# FluoroDuino.net
KiCad netlist of a schematic drawn in EAGLE
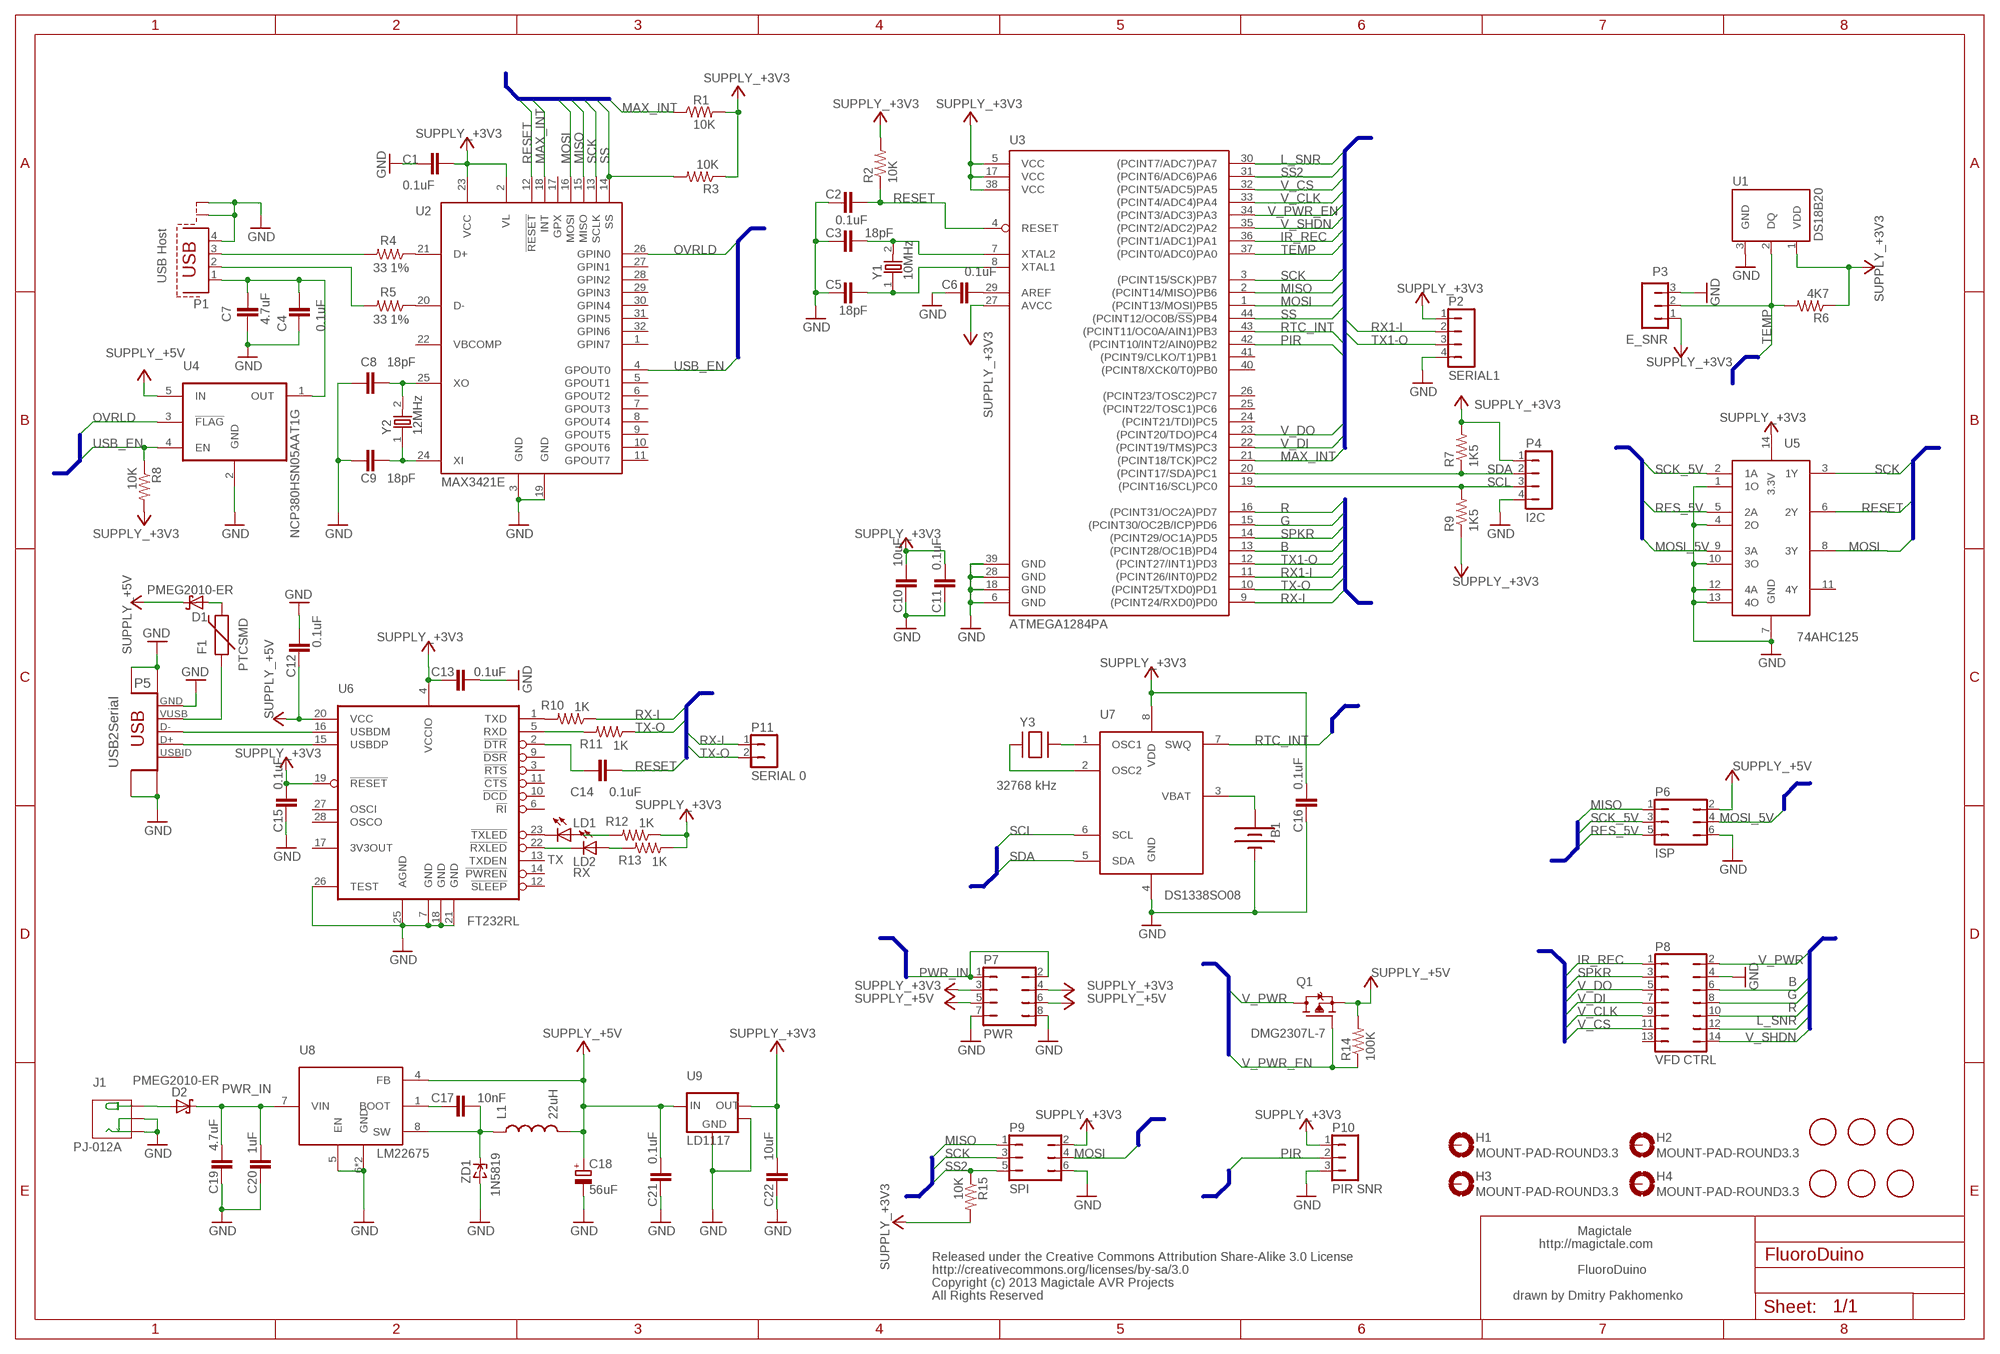
[diagram p0: schematic, sheet 1]

(export (version "E")
  (design (tool "Eeschema 10.0.6"))
  (components
    (comp (ref "B1")
      (value "BATTERY20PTH")
      (footprint "eagle-import:BATTCOM_20MM_PTH")
      (libsource (lib "eagle-import") (part "BATTERY20PTH"))
    )
    (comp (ref "C1")
      (value "0.1uF")
      (footprint "eagle-import:C1206")
      (libsource (lib "eagle-import") (part "CAPACITOR_NPOL-1206"))
    )
    (comp (ref "C2")
      (value "0.1uF")
      (footprint "eagle-import:C1206")
      (libsource (lib "eagle-import") (part "CAPACITOR_NPOL-1206"))
    )
    (comp (ref "C3")
      (value "18pF")
      (footprint "eagle-import:C1206")
      (libsource (lib "eagle-import") (part "CAPACITOR_NPOL-1206"))
    )
    (comp (ref "C4")
      (value "0.1uF")
      (footprint "eagle-import:C1206")
      (libsource (lib "eagle-import") (part "CAPACITOR_NPOL-1206"))
    )
    (comp (ref "C5")
      (value "18pF")
      (footprint "eagle-import:C1206")
      (libsource (lib "eagle-import") (part "CAPACITOR_NPOL-1206"))
    )
    (comp (ref "C6")
      (value "0.1uF")
      (footprint "eagle-import:C1206")
      (libsource (lib "eagle-import") (part "CAPACITOR_NPOL-1206"))
    )
    (comp (ref "C7")
      (value "4.7uF")
      (footprint "eagle-import:C1206")
      (libsource (lib "eagle-import") (part "CAPACITOR_NPOL-1206"))
    )
    (comp (ref "C8")
      (value "18pF")
      (footprint "eagle-import:C1206")
      (libsource (lib "eagle-import") (part "CAPACITOR_NPOL-1206"))
    )
    (comp (ref "C9")
      (value "18pF")
      (footprint "eagle-import:C1206")
      (libsource (lib "eagle-import") (part "CAPACITOR_NPOL-1206"))
    )
    (comp (ref "C10")
      (value "10uF")
      (footprint "eagle-import:C1206")
      (libsource (lib "eagle-import") (part "CAPACITOR_NPOL-1206"))
    )
    (comp (ref "C11")
      (value "0.1uF")
      (footprint "eagle-import:C1206")
      (libsource (lib "eagle-import") (part "CAPACITOR_NPOL-1206"))
    )
    (comp (ref "C12")
      (value "0.1uF")
      (footprint "eagle-import:C1206")
      (libsource (lib "eagle-import") (part "CAPACITOR_NPOL-1206"))
    )
    (comp (ref "C13")
      (value "0.1uF")
      (footprint "eagle-import:C1206")
      (libsource (lib "eagle-import") (part "CAPACITOR_NPOL-1206"))
    )
    (comp (ref "C14")
      (value "0.1uF")
      (footprint "eagle-import:C1206")
      (libsource (lib "eagle-import") (part "CAPACITOR_NPOL-1206"))
    )
    (comp (ref "C15")
      (value "0.1uF")
      (footprint "eagle-import:C1206")
      (libsource (lib "eagle-import") (part "CAPACITOR_NPOL-1206"))
    )
    (comp (ref "C16")
      (value "0.1uF")
      (footprint "eagle-import:C1206")
      (libsource (lib "eagle-import") (part "CAPACITOR_NPOL-1206"))
    )
    (comp (ref "C17")
      (value "10nF")
      (footprint "eagle-import:C1206")
      (libsource (lib "eagle-import") (part "CAPACITOR_NPOL-1206"))
    )
    (comp (ref "C18")
      (value "56uF")
      (footprint "eagle-import:PANASONIC_C")
      (libsource (lib "eagle-import") (part "CAPACITOR_POL"))
    )
    (comp (ref "C19")
      (value "4.7uF")
      (footprint "eagle-import:C1206")
      (libsource (lib "eagle-import") (part "CAPACITOR_NPOL-1206"))
    )
    (comp (ref "C20")
      (value "1uF")
      (footprint "eagle-import:C1206")
      (libsource (lib "eagle-import") (part "CAPACITOR_NPOL-1206"))
    )
    (comp (ref "C21")
      (value "0.1uF")
      (footprint "eagle-import:C1206")
      (libsource (lib "eagle-import") (part "CAPACITOR_NPOL-1206"))
    )
    (comp (ref "C22")
      (value "10uF")
      (footprint "eagle-import:C1206")
      (libsource (lib "eagle-import") (part "CAPACITOR_NPOL-1206"))
    )
    (comp (ref "D1")
      (value "PMEG2010-ER")
      (footprint "eagle-import:SOD123")
      (libsource (lib "eagle-import") (part "PMEG2010-ER"))
    )
    (comp (ref "D2")
      (value "PMEG2010-ER")
      (footprint "eagle-import:SOD123")
      (libsource (lib "eagle-import") (part "PMEG2010-ER"))
    )
    (comp (ref "F1")
      (value "PTCSMD")
      (footprint "eagle-import:PTC-1206")
      (libsource (lib "eagle-import") (part "PTCSMD"))
    )
    (comp (ref "FIDUTIAL1")
      (value "FIDUCIAL")
      (footprint "eagle-import:FIDUCIAL_1MM")
      (libsource (lib "eagle-import") (part "FIDUCIAL"))
    )
    (comp (ref "FIDUTIAL2")
      (value "FIDUCIAL")
      (footprint "eagle-import:FIDUCIAL_1MM")
      (libsource (lib "eagle-import") (part "FIDUCIAL"))
    )
    (comp (ref "FIDUTIAL3")
      (value "FIDUCIAL")
      (footprint "eagle-import:FIDUCIAL_1MM")
      (libsource (lib "eagle-import") (part "FIDUCIAL"))
    )
    (comp (ref "FIDUTIAL4")
      (value "FIDUCIAL")
      (footprint "eagle-import:FIDUCIAL_1MM")
      (libsource (lib "eagle-import") (part "FIDUCIAL"))
    )
    (comp (ref "FIDUTIAL5")
      (value "FIDUCIAL")
      (footprint "eagle-import:FIDUCIAL_1MM")
      (libsource (lib "eagle-import") (part "FIDUCIAL"))
    )
    (comp (ref "FIDUTIAL6")
      (value "FIDUCIAL")
      (footprint "eagle-import:FIDUCIAL_1MM")
      (libsource (lib "eagle-import") (part "FIDUCIAL"))
    )
    (comp (ref "H1")
      (value "MOUNT-PAD-ROUND3.3")
      (footprint "eagle-import:3,3-PAD")
      (libsource (lib "eagle-import") (part "MOUNT-PAD-ROUND3.3"))
    )
    (comp (ref "H2")
      (value "MOUNT-PAD-ROUND3.3")
      (footprint "eagle-import:3,3-PAD")
      (libsource (lib "eagle-import") (part "MOUNT-PAD-ROUND3.3"))
    )
    (comp (ref "H3")
      (value "MOUNT-PAD-ROUND3.3")
      (footprint "eagle-import:3,3-PAD")
      (libsource (lib "eagle-import") (part "MOUNT-PAD-ROUND3.3"))
    )
    (comp (ref "H4")
      (value "MOUNT-PAD-ROUND3.3")
      (footprint "eagle-import:3,3-PAD")
      (libsource (lib "eagle-import") (part "MOUNT-PAD-ROUND3.3"))
    )
    (comp (ref "J1")
      (value "PJ-012A")
      (footprint "eagle-import:PJ-012A")
      (libsource (lib "eagle-import") (part "PJ-012A"))
    )
    (comp (ref "L1")
      (value "22uH")
      (footprint "eagle-import:VLC6045")
      (libsource (lib "eagle-import") (part "INDUCTOR"))
    )
    (comp (ref "LD1")
      (value "TX")
      (footprint "eagle-import:CHIPLED_1206")
      (libsource (lib "eagle-import") (part "LEDCHIPLED_1206"))
    )
    (comp (ref "LD2")
      (value "RX")
      (footprint "eagle-import:CHIPLED_1206")
      (libsource (lib "eagle-import") (part "LEDCHIPLED_1206"))
    )
    (comp (ref "P1")
      (value "USB Host")
      (footprint "eagle-import:USB-A-VER")
      (libsource (lib "eagle-import") (part "USB-AVERT"))
    )
    (comp (ref "P2")
      (value "SERIAL1")
      (footprint "eagle-import:CONN_HEADER_1X04")
      (libsource (lib "eagle-import") (part "CONN_HEADER_1X04STRAIGHT"))
    )
    (comp (ref "P3")
      (value "E_SNR")
      (footprint "eagle-import:CONN_HEADER_1X03")
      (fields (field (name "F_PIN") "1") (field (name "L_PIN") "3"))
      (libsource (lib "eagle-import") (part "CONN_HEADER_1X03STRAIGHT"))
    )
    (comp (ref "P4")
      (value "I2C")
      (footprint "eagle-import:CONN_HEADER_1X04")
      (fields (field (name "F_PIN") "1") (field (name "L_PIN") "4"))
      (libsource (lib "eagle-import") (part "CONN_HEADER_1X04STRAIGHT"))
    )
    (comp (ref "P5")
      (value "USB2Serial")
      (footprint "eagle-import:CONN_USB_MINI_RA")
      (fields (field (name "DIGIKEY") "732-2735-ND"))
      (libsource (lib "eagle-import") (part "CON-USB-F-MINI-B-RA"))
    )
    (comp (ref "P6")
      (value "ISP")
      (footprint "eagle-import:CONN_HEADER_2X03")
      (fields (field (name "F_PIN") "1") (field (name "L_PIN") "5"))
      (libsource (lib "eagle-import") (part "CONN_HEADER_2X03"))
    )
    (comp (ref "P7")
      (value "PWR")
      (footprint "eagle-import:CONN_HEADER_2X04")
      (fields (field (name "F_PIN") "1") (field (name "L_PIN") "7"))
      (libsource (lib "eagle-import") (part "CONN_HEADER_2X04"))
    )
    (comp (ref "P8")
      (value "VFD CTRL")
      (footprint "eagle-import:CONN_HEADER_2X07_F_MIRR")
      (libsource (lib "eagle-import") (part "CONN_HEADER_2X07F_MIRR"))
    )
    (comp (ref "P9")
      (value "SPI")
      (footprint "eagle-import:CONN_HEADER_2X03")
      (fields (field (name "F_PIN") "1") (field (name "L_PIN") "5"))
      (libsource (lib "eagle-import") (part "CONN_HEADER_2X03"))
    )
    (comp (ref "P10")
      (value "PIR SNR")
      (footprint "eagle-import:CONN_HEADER_1X03")
      (fields (field (name "F_PIN") "1") (field (name "L_PIN") "3"))
      (libsource (lib "eagle-import") (part "CONN_HEADER_1X03STRAIGHT"))
    )
    (comp (ref "P11")
      (value "SERIAL 0")
      (footprint "eagle-import:CONN_HEADER_1X02")
      (libsource (lib "eagle-import") (part "CONN_HEADER_1X02"))
    )
    (comp (ref "Q1")
      (value "DMG2307L-7")
      (footprint "eagle-import:SOT-23")
      (libsource (lib "eagle-import") (part "TRANSISTOR_FET_TSM2301CX"))
    )
    (comp (ref "R1")
      (value "10K")
      (footprint "eagle-import:R1206")
      (libsource (lib "eagle-import") (part "RESISTOR-1206"))
    )
    (comp (ref "R2")
      (value "10K")
      (footprint "eagle-import:R1206")
      (libsource (lib "eagle-import") (part "RESISTOR-1206"))
    )
    (comp (ref "R3")
      (value "10K")
      (footprint "eagle-import:R1206")
      (libsource (lib "eagle-import") (part "RESISTOR-1206"))
    )
    (comp (ref "R4")
      (value "33 1%")
      (footprint "eagle-import:R1206")
      (libsource (lib "eagle-import") (part "RESISTOR-1206"))
    )
    (comp (ref "R5")
      (value "33 1%")
      (footprint "eagle-import:R1206")
      (libsource (lib "eagle-import") (part "RESISTOR-1206"))
    )
    (comp (ref "R6")
      (value "4K7")
      (footprint "eagle-import:R1206")
      (libsource (lib "eagle-import") (part "RESISTOR-1206"))
    )
    (comp (ref "R7")
      (value "1K5")
      (footprint "eagle-import:R1206")
      (libsource (lib "eagle-import") (part "RESISTOR-1206"))
    )
    (comp (ref "R8")
      (value "10K")
      (footprint "eagle-import:R1206")
      (libsource (lib "eagle-import") (part "RESISTOR-1206"))
    )
    (comp (ref "R9")
      (value "1K5")
      (footprint "eagle-import:R1206")
      (libsource (lib "eagle-import") (part "RESISTOR-1206"))
    )
    (comp (ref "R10")
      (value "1K")
      (footprint "eagle-import:R1206")
      (libsource (lib "eagle-import") (part "RESISTOR-1206"))
    )
    (comp (ref "R11")
      (value "1K")
      (footprint "eagle-import:R1206")
      (libsource (lib "eagle-import") (part "RESISTOR-1206"))
    )
    (comp (ref "R12")
      (value "1K")
      (footprint "eagle-import:R1206")
      (libsource (lib "eagle-import") (part "RESISTOR-1206"))
    )
    (comp (ref "R13")
      (value "1K")
      (footprint "eagle-import:R1206")
      (libsource (lib "eagle-import") (part "RESISTOR-1206"))
    )
    (comp (ref "R14")
      (value "100K")
      (footprint "eagle-import:R1206")
      (libsource (lib "eagle-import") (part "RESISTOR-1206"))
    )
    (comp (ref "R15")
      (value "10K")
      (footprint "eagle-import:R1206")
      (libsource (lib "eagle-import") (part "RESISTOR-1206"))
    )
    (comp (ref "U$")
      (value "MT_LOGOCOMPACT")
      (footprint "eagle-import:MT_LOGO_COMPACT")
      (libsource (lib "eagle-import") (part "MT_LOGOCOMPACT"))
    )
    (comp (ref "U1")
      (value "DS18B20")
      (footprint "eagle-import:TO-92-AMMO")
      (libsource (lib "eagle-import") (part "DS18B20"))
    )
    (comp (ref "U2")
      (value "MAX3421E")
      (footprint "eagle-import:TQFP32-08")
      (libsource (lib "eagle-import") (part "MAXIM_MAX3421E"))
    )
    (comp (ref "U3")
      (value "ATMEGA1284PA")
      (footprint "eagle-import:TQFP44")
      (fields (field (name "MPN") "ATMEGA1284P-10AU"))
      (libsource (lib "eagle-import") (part "ATMEGA1284PA"))
    )
    (comp (ref "U4")
      (value "NCP380HSN05AAT1G")
      (footprint "eagle-import:SOT23-5")
      (libsource (lib "eagle-import") (part "POWERSW_FIX-SOT5-1"))
    )
    (comp (ref "U5")
      (value "74AHC125")
      (footprint "eagle-import:SO014")
      (libsource (lib "eagle-import") (part "CH_LOGIC_74125_33V-SO"))
    )
    (comp (ref "U6")
      (value "FT232RL")
      (footprint "eagle-import:SSOP-28")
      (libsource (lib "eagle-import") (part "IC_FT232RL"))
    )
    (comp (ref "U7")
      (value "DS1338SO08")
      (footprint "eagle-import:SO08")
      (libsource (lib "eagle-import") (part "ICS_DS1338SO08"))
    )
    (comp (ref "U8")
      (value "LM22675")
      (footprint "eagle-import:SO08_POWER_PAD")
      (libsource (lib "eagle-import") (part "ICS_LM22675"))
    )
    (comp (ref "U9")
      (value "LD1117")
      (footprint "eagle-import:SOT223")
      (libsource (lib "eagle-import") (part "V_REG_LD1117SOT223"))
    )
    (comp (ref "Y1")
      (value "10MHz")
      (footprint "eagle-import:XTAL_4X6")
      (libsource (lib "eagle-import") (part "OSC-XTAL-12M"))
    )
    (comp (ref "Y2")
      (value "12MHz")
      (footprint "eagle-import:XTAL_4X6")
      (libsource (lib "eagle-import") (part "OSC-XTAL-12M"))
    )
    (comp (ref "Y3")
      (value "32768 kHz")
      (footprint "eagle-import:XTAL3215")
      (libsource (lib "eagle-import") (part "XTAL-3.2X1.5"))
    )
    (comp (ref "ZD1")
      (value "1N5819")
      (footprint "eagle-import:SOD123")
      (libsource (lib "eagle-import") (part "ZENERSOD-123"))
    )
  )
  (nets
    (net (code "1") (name "/B") (class "Default")
      (node (ref "P8") (pin "6") (pinfunction "6_6") (pintype "passive"))
      (node (ref "U3") (pin "13") (pinfunction "(PCINT28/OC1B)PD4_13") (pintype "bidirectional"))
    )
    (net (code "2") (name "/G") (class "Default")
      (node (ref "P8") (pin "8") (pinfunction "8_8") (pintype "passive"))
      (node (ref "U3") (pin "15") (pinfunction "(PCINT30/OC2B/ICP)PD6_15") (pintype "bidirectional"))
    )
    (net (code "3") (name "/IR_REC") (class "Default")
      (node (ref "P8") (pin "1") (pinfunction "1_1") (pintype "passive"))
      (node (ref "U3") (pin "36") (pinfunction "(PCINT1/ADC1)PA1_36") (pintype "bidirectional"))
    )
    (net (code "4") (name "/L_SNR") (class "Default")
      (node (ref "P8") (pin "12") (pinfunction "12_12") (pintype "passive"))
      (node (ref "U3") (pin "30") (pinfunction "(PCINT7/ADC7)PA7_30") (pintype "bidirectional"))
    )
    (net (code "5") (name "/MAX_INT") (class "Default")
      (node (ref "R1") (pin "1") (pinfunction "1_1") (pintype "passive"))
      (node (ref "U2") (pin "18") (pinfunction "INT_18") (pintype "output"))
      (node (ref "U3") (pin "21") (pinfunction "(PCINT18/TCK)PC2_21") (pintype "output"))
    )
    (net (code "6") (name "/MISO") (class "Default")
      (node (ref "P6") (pin "1") (pinfunction "1_1") (pintype "passive"))
      (node (ref "P9") (pin "1") (pinfunction "1_1") (pintype "passive"))
      (node (ref "U2") (pin "15") (pinfunction "MISO_15") (pintype "output"))
      (node (ref "U3") (pin "2") (pinfunction "(PCINT14/MISO)PB6_2") (pintype "bidirectional"))
    )
    (net (code "7") (name "/MOSI") (class "Default")
      (node (ref "P9") (pin "4") (pinfunction "4_4") (pintype "passive"))
      (node (ref "U2") (pin "16") (pinfunction "MOSI_16") (pintype "input"))
      (node (ref "U3") (pin "1") (pinfunction "(PCINT13/MOSI)PB5_1") (pintype "bidirectional"))
      (node (ref "U5") (pin "8") (pinfunction "3Y_8") (pintype "output"))
    )
    (net (code "8") (name "/MOSI_5V") (class "Default")
      (node (ref "P6") (pin "4") (pinfunction "4_4") (pintype "passive"))
      (node (ref "U5") (pin "9") (pinfunction "3A_9") (pintype "input"))
    )
    (net (code "9") (name "/OVRLD") (class "Default")
      (node (ref "U2") (pin "26") (pinfunction "GPIN0_26") (pintype "input"))
      (node (ref "U4") (pin "3") (pinfunction "~{FLAG}_3") (pintype "bidirectional"))
    )
    (net (code "10") (name "/PIR") (class "Default")
      (node (ref "P10") (pin "2") (pinfunction "2_2") (pintype "passive"))
      (node (ref "U3") (pin "42") (pinfunction "(PCINT10/INT2/AIN0)PB2_42") (pintype "bidirectional"))
    )
    (net (code "11") (name "/PWR_IN") (class "Default")
      (node (ref "C19") (pin "2") (pinfunction "2_2") (pintype "passive"))
      (node (ref "C20") (pin "2") (pinfunction "2_2") (pintype "passive"))
      (node (ref "D2") (pin "C") (pinfunction "C_C") (pintype "passive"))
      (node (ref "P7") (pin "1") (pinfunction "1_1") (pintype "passive"))
      (node (ref "P7") (pin "2") (pinfunction "2_2") (pintype "passive"))
      (node (ref "U8") (pin "7") (pinfunction "VIN_7") (pintype "power_in"))
    )
    (net (code "12") (name "/R") (class "Default")
      (node (ref "P8") (pin "10") (pinfunction "10_10") (pintype "passive"))
      (node (ref "U3") (pin "16") (pinfunction "(PCINT31/OC2A)PD7_16") (pintype "bidirectional"))
    )
    (net (code "13") (name "/RESET") (class "Default")
      (node (ref "C14") (pin "1") (pinfunction "1_1") (pintype "passive"))
      (node (ref "C2") (pin "2") (pinfunction "2_2") (pintype "passive"))
      (node (ref "R2") (pin "1") (pinfunction "1_1") (pintype "passive"))
      (node (ref "U2") (pin "12") (pinfunction "~{RESET}_12") (pintype "input"))
      (node (ref "U3") (pin "4") (pinfunction "RESET_4") (pintype "input"))
      (node (ref "U5") (pin "6") (pinfunction "2Y_6") (pintype "output"))
    )
    (net (code "14") (name "/RES_5V") (class "Default")
      (node (ref "P6") (pin "5") (pinfunction "5_5") (pintype "passive"))
      (node (ref "U5") (pin "5") (pinfunction "2A_5") (pintype "input"))
    )
    (net (code "15") (name "/RTC_INT") (class "Default")
      (node (ref "U3") (pin "43") (pinfunction "(PCINT11/OC0A/AIN1)PB3_43") (pintype "bidirectional"))
      (node (ref "U7") (pin "7") (pinfunction "SWQ_7") (pintype "bidirectional"))
    )
    (net (code "16") (name "/RX-I") (class "Default")
      (node (ref "P11") (pin "1") (pinfunction "1_1") (pintype "passive"))
      (node (ref "R10") (pin "1") (pinfunction "1_1") (pintype "passive"))
      (node (ref "U3") (pin "9") (pinfunction "(PCINT24/RXD0)PD0_9") (pintype "bidirectional"))
    )
    (net (code "17") (name "/RX1-I") (class "Default")
      (node (ref "P2") (pin "2") (pinfunction "2_2") (pintype "passive"))
      (node (ref "U3") (pin "11") (pinfunction "(PCINT26/INT0)PD2_11") (pintype "bidirectional"))
    )
    (net (code "18") (name "/SCK") (class "Default")
      (node (ref "P9") (pin "3") (pinfunction "3_3") (pintype "passive"))
      (node (ref "U2") (pin "13") (pinfunction "SCLK_13") (pintype "input"))
      (node (ref "U3") (pin "3") (pinfunction "(PCINT15/SCK)PB7_3") (pintype "bidirectional"))
      (node (ref "U5") (pin "3") (pinfunction "1Y_3") (pintype "output"))
    )
    (net (code "19") (name "/SCK_5V") (class "Default")
      (node (ref "P6") (pin "3") (pinfunction "3_3") (pintype "passive"))
      (node (ref "U5") (pin "2") (pinfunction "1A_2") (pintype "input"))
    )
    (net (code "20") (name "/SCL") (class "Default")
      (node (ref "P4") (pin "3") (pinfunction "3_3") (pintype "passive"))
      (node (ref "R9") (pin "2") (pinfunction "2_2") (pintype "passive"))
      (node (ref "U3") (pin "19") (pinfunction "(PCINT16/SCL)PC0_19") (pintype "output"))
      (node (ref "U7") (pin "6") (pinfunction "SCL_6") (pintype "bidirectional"))
    )
    (net (code "21") (name "/SDA") (class "Default")
      (node (ref "P4") (pin "2") (pinfunction "2_2") (pintype "passive"))
      (node (ref "R7") (pin "1") (pinfunction "1_1") (pintype "passive"))
      (node (ref "U3") (pin "20") (pinfunction "(PCINT17/SDA)PC1_20") (pintype "output"))
      (node (ref "U7") (pin "5") (pinfunction "SDA_5") (pintype "bidirectional"))
    )
    (net (code "22") (name "/SPKR") (class "Default")
      (node (ref "P8") (pin "3") (pinfunction "3_3") (pintype "passive"))
      (node (ref "U3") (pin "14") (pinfunction "(PCINT29/OC1A)PD5_14") (pintype "bidirectional"))
    )
    (net (code "23") (name "/SS") (class "Default")
      (node (ref "R3") (pin "2") (pinfunction "2_2") (pintype "passive"))
      (node (ref "U2") (pin "14") (pinfunction "SS_14") (pintype "input"))
      (node (ref "U3") (pin "44") (pinfunction "(PCINT12/OC0B/~{SS})PB4_44") (pintype "bidirectional"))
    )
    (net (code "24") (name "/SS2") (class "Default")
      (node (ref "P9") (pin "5") (pinfunction "5_5") (pintype "passive"))
      (node (ref "R15") (pin "1") (pinfunction "1_1") (pintype "passive"))
      (node (ref "U3") (pin "31") (pinfunction "(PCINT6/ADC6)PA6_31") (pintype "bidirectional"))
    )
    (net (code "25") (name "/TEMP") (class "Default")
      (node (ref "P3") (pin "2") (pinfunction "2_2") (pintype "passive"))
      (node (ref "R6") (pin "2") (pinfunction "2_2") (pintype "passive"))
      (node (ref "U1") (pin "2") (pinfunction "DQ_2") (pintype "bidirectional"))
      (node (ref "U3") (pin "37") (pinfunction "(PCINT0/ADC0)PA0_37") (pintype "bidirectional"))
    )
    (net (code "26") (name "/TX-O") (class "Default")
      (node (ref "P11") (pin "2") (pinfunction "2_2") (pintype "passive"))
      (node (ref "R11") (pin "1") (pinfunction "1_1") (pintype "passive"))
      (node (ref "U3") (pin "10") (pinfunction "(PCINT25/TXD0)PD1_10") (pintype "bidirectional"))
    )
    (net (code "27") (name "/TX1-O") (class "Default")
      (node (ref "P2") (pin "3") (pinfunction "3_3") (pintype "passive"))
      (node (ref "U3") (pin "12") (pinfunction "(PCINT27/INT1)PD3_12") (pintype "bidirectional"))
    )
    (net (code "28") (name "/USB_EN") (class "Default")
      (node (ref "R8") (pin "1") (pinfunction "1_1") (pintype "passive"))
      (node (ref "U2") (pin "4") (pinfunction "GPOUT0_4") (pintype "output"))
      (node (ref "U4") (pin "4") (pinfunction "EN_4") (pintype "bidirectional"))
    )
    (net (code "29") (name "/V_CLK") (class "Default")
      (node (ref "P8") (pin "9") (pinfunction "9_9") (pintype "passive"))
      (node (ref "U3") (pin "33") (pinfunction "(PCINT4/ADC4)PA4_33") (pintype "bidirectional"))
    )
    (net (code "30") (name "/V_CS") (class "Default")
      (node (ref "P8") (pin "11") (pinfunction "11_11") (pintype "passive"))
      (node (ref "U3") (pin "32") (pinfunction "(PCINT5/ADC5)PA5_32") (pintype "bidirectional"))
    )
    (net (code "31") (name "/V_DI") (class "Default")
      (node (ref "P8") (pin "7") (pinfunction "7_7") (pintype "passive"))
      (node (ref "U3") (pin "22") (pinfunction "(PCINT19/TMS)PC3_22") (pintype "output"))
    )
    (net (code "32") (name "/V_DO") (class "Default")
      (node (ref "P8") (pin "5") (pinfunction "5_5") (pintype "passive"))
      (node (ref "U3") (pin "23") (pinfunction "(PCINT20/TDO)PC4_23") (pintype "output"))
    )
    (net (code "33") (name "/V_PWR") (class "Default")
      (node (ref "P8") (pin "2") (pinfunction "2_2") (pintype "passive"))
      (node (ref "Q1") (pin "3") (pinfunction "D_3") (pintype "passive"))
    )
    (net (code "34") (name "/V_PWR_EN") (class "Default")
      (node (ref "Q1") (pin "1") (pinfunction "G_1") (pintype "passive"))
      (node (ref "R14") (pin "1") (pinfunction "1_1") (pintype "passive"))
      (node (ref "U3") (pin "34") (pinfunction "(PCINT3/ADC3)PA3_34") (pintype "bidirectional"))
    )
    (net (code "35") (name "/V_SHDN") (class "Default")
      (node (ref "P8") (pin "14") (pinfunction "14_14") (pintype "passive"))
      (node (ref "U3") (pin "35") (pinfunction "(PCINT2/ADC2)PA2_35") (pintype "bidirectional"))
    )
    (net (code "36") (name "GND") (class "Default")
      (node (ref "B1") (pin "2") (pinfunction "-_2") (pintype "power_in"))
      (node (ref "C1") (pin "2") (pinfunction "2_2") (pintype "passive"))
      (node (ref "C10") (pin "1") (pinfunction "1_1") (pintype "passive"))
      (node (ref "C11") (pin "1") (pinfunction "1_1") (pintype "passive"))
      (node (ref "C12") (pin "2") (pinfunction "2_2") (pintype "passive"))
      (node (ref "C13") (pin "2") (pinfunction "2_2") (pintype "passive"))
      (node (ref "C15") (pin "1") (pinfunction "1_1") (pintype "passive"))
      (node (ref "C16") (pin "1") (pinfunction "1_1") (pintype "passive"))
      (node (ref "C18") (pin "-") (pinfunction "-_-") (pintype "passive"))
      (node (ref "C19") (pin "1") (pinfunction "1_1") (pintype "passive"))
      (node (ref "C2") (pin "1") (pinfunction "1_1") (pintype "passive"))
      (node (ref "C20") (pin "1") (pinfunction "1_1") (pintype "passive"))
      (node (ref "C21") (pin "1") (pinfunction "1_1") (pintype "passive"))
      (node (ref "C22") (pin "1") (pinfunction "1_1") (pintype "passive"))
      (node (ref "C3") (pin "1") (pinfunction "1_1") (pintype "passive"))
      (node (ref "C4") (pin "2") (pinfunction "2_2") (pintype "passive"))
      (node (ref "C5") (pin "1") (pinfunction "1_1") (pintype "passive"))
      (node (ref "C6") (pin "1") (pinfunction "1_1") (pintype "passive"))
      (node (ref "C7") (pin "1") (pinfunction "1_1") (pintype "passive"))
      (node (ref "C8") (pin "1") (pinfunction "1_1") (pintype "passive"))
      (node (ref "C9") (pin "1") (pinfunction "1_1") (pintype "passive"))
      (node (ref "J1") (pin "2") (pinfunction "2_2") (pintype "bidirectional"))
      (node (ref "J1") (pin "3") (pinfunction "3_3") (pintype "bidirectional"))
      (node (ref "P1") (pin "4") (pinfunction "4_4") (pintype "passive"))
      (node (ref "P1") (pin "S1") (pinfunction "S1_S1") (pintype "passive"))
      (node (ref "P1") (pin "S2") (pinfunction "S2_S2") (pintype "passive"))
      (node (ref "P10") (pin "3") (pinfunction "3_3") (pintype "passive"))
      (node (ref "P2") (pin "4") (pinfunction "4_4") (pintype "passive"))
      (node (ref "P3") (pin "3") (pinfunction "3_3") (pintype "passive"))
      (node (ref "P4") (pin "4") (pinfunction "4_4") (pintype "passive"))
      (node (ref "P5") (pin "5") (pinfunction "GND_5") (pintype "bidirectional"))
      (node (ref "P5") (pin "S1") (pinfunction "BODY_S1") (pintype "tri_state"))
      (node (ref "P5") (pin "S2") (pinfunction "BODY_S2") (pintype "tri_state"))
      (node (ref "P5") (pin "S3") (pinfunction "BODY_S3") (pintype "tri_state"))
      (node (ref "P5") (pin "S4") (pinfunction "BODY_S4") (pintype "tri_state"))
      (node (ref "P6") (pin "6") (pinfunction "6_6") (pintype "passive"))
      (node (ref "P7") (pin "7") (pinfunction "7_7") (pintype "passive"))
      (node (ref "P7") (pin "8") (pinfunction "8_8") (pintype "passive"))
      (node (ref "P8") (pin "4") (pinfunction "4_4") (pintype "passive"))
      (node (ref "P9") (pin "6") (pinfunction "6_6") (pintype "passive"))
      (node (ref "U1") (pin "3") (pinfunction "GND_3") (pintype "power_in"))
      (node (ref "U2") (pin "19") (pinfunction "GND_19") (pintype "power_in"))
      (node (ref "U2") (pin "3") (pinfunction "GND_3") (pintype "power_in"))
      (node (ref "U3") (pin "18") (pinfunction "GND_18") (pintype "power_in"))
      (node (ref "U3") (pin "28") (pinfunction "GND_28") (pintype "power_in"))
      (node (ref "U3") (pin "39") (pinfunction "GND_39") (pintype "power_in"))
      (node (ref "U3") (pin "6") (pinfunction "GND_6") (pintype "power_in"))
      (node (ref "U4") (pin "2") (pinfunction "GND_2") (pintype "bidirectional"))
      (node (ref "U5") (pin "1") (pinfunction "1O_1") (pintype "input"))
      (node (ref "U5") (pin "10") (pinfunction "3O_10") (pintype "input"))
      (node (ref "U5") (pin "12") (pinfunction "4A_12") (pintype "input"))
      (node (ref "U5") (pin "13") (pinfunction "4O_13") (pintype "input"))
      (node (ref "U5") (pin "4") (pinfunction "2O_4") (pintype "input"))
      (node (ref "U5") (pin "7") (pinfunction "GND_7") (pintype "passive"))
      (node (ref "U6") (pin "18") (pinfunction "GND_18") (pintype "bidirectional"))
      (node (ref "U6") (pin "21") (pinfunction "GND_21") (pintype "bidirectional"))
      (node (ref "U6") (pin "25") (pinfunction "AGND_25") (pintype "bidirectional"))
      (node (ref "U6") (pin "26") (pinfunction "TEST_26") (pintype "bidirectional"))
      (node (ref "U6") (pin "7") (pinfunction "GND_7") (pintype "bidirectional"))
      (node (ref "U7") (pin "4") (pinfunction "GND_4") (pintype "bidirectional"))
      (node (ref "U8") (pin "5") (pinfunction "EN_5") (pintype "bidirectional"))
      (node (ref "U8") (pin "6") (pinfunction "GND_6") (pintype "power_in"))
      (node (ref "U8") (pin "BODY@1") (pinfunction "GND_BODY@1") (pintype "power_in"))
      (node (ref "U9") (pin "1") (pinfunction "GND_1") (pintype "input"))
      (node (ref "U9") (pin "4") (pinfunction "OUT_4") (pintype "output"))
      (node (ref "ZD1") (pin "A") (pinfunction "A_A") (pintype "passive"))
    )
    (net (code "37") (name "Net-(B1-+)") (class "Default")
      (node (ref "B1") (pin "1") (pinfunction "+_1") (pintype "power_in"))
      (node (ref "U7") (pin "3") (pinfunction "VBAT_3") (pintype "bidirectional"))
    )
    (net (code "38") (name "Net-(D1-PadA)") (class "Default")
      (node (ref "D1") (pin "A") (pinfunction "A_A") (pintype "passive"))
      (node (ref "F1") (pin "2") (pinfunction "2_2") (pintype "bidirectional"))
    )
    (net (code "39") (name "Net-(D2-PadA)") (class "Default")
      (node (ref "D2") (pin "A") (pinfunction "A_A") (pintype "passive"))
      (node (ref "J1") (pin "1") (pinfunction "1_1") (pintype "bidirectional"))
    )
    (net (code "40") (name "Net-(LD1-PadA)") (class "Default")
      (node (ref "LD1") (pin "A") (pinfunction "A_A") (pintype "passive"))
      (node (ref "R12") (pin "2") (pinfunction "2_2") (pintype "passive"))
    )
    (net (code "41") (name "Net-(LD2-PadA)") (class "Default")
      (node (ref "LD2") (pin "A") (pinfunction "A_A") (pintype "passive"))
      (node (ref "R13") (pin "2") (pinfunction "2_2") (pintype "passive"))
    )
    (net (code "42") (name "Net-(P1-Pad2)") (class "Default")
      (node (ref "P1") (pin "2") (pinfunction "2_2") (pintype "passive"))
      (node (ref "R5") (pin "2") (pinfunction "2_2") (pintype "passive"))
    )
    (net (code "43") (name "Net-(P1-Pad3)") (class "Default")
      (node (ref "P1") (pin "3") (pinfunction "3_3") (pintype "passive"))
      (node (ref "R4") (pin "2") (pinfunction "2_2") (pintype "passive"))
    )
    (net (code "44") (name "Net-(P5B-D+)") (class "Default")
      (node (ref "P5") (pin "3") (pinfunction "D+_3") (pintype "bidirectional"))
      (node (ref "U6") (pin "15") (pinfunction "USBDP_15") (pintype "bidirectional"))
    )
    (net (code "45") (name "Net-(P5B-D-)") (class "Default")
      (node (ref "P5") (pin "2") (pinfunction "D-_2") (pintype "bidirectional"))
      (node (ref "U6") (pin "16") (pinfunction "USBDM_16") (pintype "bidirectional"))
    )
    (net (code "46") (name "Net-(P5B-VUSB)") (class "Default")
      (node (ref "F1") (pin "1") (pinfunction "1_1") (pintype "bidirectional"))
      (node (ref "P5") (pin "1") (pinfunction "VUSB_1") (pintype "bidirectional"))
    )
    (net (code "47") (name "Net-(U2-D+)") (class "Default")
      (node (ref "R4") (pin "1") (pinfunction "1_1") (pintype "passive"))
      (node (ref "U2") (pin "21") (pinfunction "D+_21") (pintype "bidirectional"))
    )
    (net (code "48") (name "Net-(U2-D-)") (class "Default")
      (node (ref "R5") (pin "1") (pinfunction "1_1") (pintype "passive"))
      (node (ref "U2") (pin "20") (pinfunction "D-_20") (pintype "bidirectional"))
    )
    (net (code "49") (name "Net-(U2-XI)") (class "Default")
      (node (ref "C9") (pin "2") (pinfunction "2_2") (pintype "passive"))
      (node (ref "U2") (pin "24") (pinfunction "XI_24") (pintype "input"))
      (node (ref "Y2") (pin "1") (pinfunction "1_1") (pintype "passive"))
    )
    (net (code "50") (name "Net-(U2-XO)") (class "Default")
      (node (ref "C8") (pin "2") (pinfunction "2_2") (pintype "passive"))
      (node (ref "U2") (pin "25") (pinfunction "XO_25") (pintype "output"))
      (node (ref "Y2") (pin "2") (pinfunction "2_2") (pintype "passive"))
    )
    (net (code "51") (name "Net-(U3-AREF)") (class "Default")
      (node (ref "C6") (pin "2") (pinfunction "2_2") (pintype "passive"))
      (node (ref "U3") (pin "29") (pinfunction "AREF_29") (pintype "passive"))
    )
    (net (code "52") (name "Net-(U3-XTAL1)") (class "Default")
      (node (ref "C5") (pin "2") (pinfunction "2_2") (pintype "passive"))
      (node (ref "U3") (pin "8") (pinfunction "XTAL1_8") (pintype "bidirectional"))
      (node (ref "Y1") (pin "1") (pinfunction "1_1") (pintype "passive"))
    )
    (net (code "53") (name "Net-(U3-XTAL2)") (class "Default")
      (node (ref "C3") (pin "2") (pinfunction "2_2") (pintype "passive"))
      (node (ref "U3") (pin "7") (pinfunction "XTAL2_7") (pintype "bidirectional"))
      (node (ref "Y1") (pin "2") (pinfunction "2_2") (pintype "passive"))
    )
    (net (code "54") (name "Net-(U4-OUT)") (class "Default")
      (node (ref "C4") (pin "1") (pinfunction "1_1") (pintype "passive"))
      (node (ref "C7") (pin "2") (pinfunction "2_2") (pintype "passive"))
      (node (ref "P1") (pin "1") (pinfunction "1_1") (pintype "passive"))
      (node (ref "U4") (pin "1") (pinfunction "OUT_1") (pintype "bidirectional"))
    )
    (net (code "55") (name "Net-(U6-RXD)") (class "Default")
      (node (ref "R11") (pin "2") (pinfunction "2_2") (pintype "passive"))
      (node (ref "U6") (pin "5") (pinfunction "RXD_5") (pintype "bidirectional"))
    )
    (net (code "56") (name "Net-(U6-TXD)") (class "Default")
      (node (ref "R10") (pin "2") (pinfunction "2_2") (pintype "passive"))
      (node (ref "U6") (pin "1") (pinfunction "TXD_1") (pintype "bidirectional"))
    )
    (net (code "57") (name "Net-(U6-~{DTR})") (class "Default")
      (node (ref "C14") (pin "2") (pinfunction "2_2") (pintype "passive"))
      (node (ref "U6") (pin "2") (pinfunction "~{DTR}_2") (pintype "bidirectional"))
    )
    (net (code "58") (name "Net-(U6-~{RXLED})") (class "Default")
      (node (ref "LD2") (pin "C") (pinfunction "C_C") (pintype "passive"))
      (node (ref "U6") (pin "22") (pinfunction "~{RXLED}_22") (pintype "bidirectional"))
    )
    (net (code "59") (name "Net-(U6-~{TXLED})") (class "Default")
      (node (ref "LD1") (pin "C") (pinfunction "C_C") (pintype "passive"))
      (node (ref "U6") (pin "23") (pinfunction "~{TXLED}_23") (pintype "bidirectional"))
    )
    (net (code "60") (name "Net-(U7-OSC1)") (class "Default")
      (node (ref "U7") (pin "1") (pinfunction "OSC1_1") (pintype "bidirectional"))
      (node (ref "Y3") (pin "P$2") (pinfunction "P$2_P$2") (pintype "bidirectional"))
    )
    (net (code "61") (name "Net-(U7-OSC2)") (class "Default")
      (node (ref "U7") (pin "2") (pinfunction "OSC2_2") (pintype "bidirectional"))
      (node (ref "Y3") (pin "P$1") (pinfunction "P$1_P$1") (pintype "bidirectional"))
    )
    (net (code "62") (name "Net-(U8-BOOT)") (class "Default")
      (node (ref "C17") (pin "1") (pinfunction "1_1") (pintype "passive"))
      (node (ref "U8") (pin "1") (pinfunction "BOOT_1") (pintype "input"))
    )
    (net (code "63") (name "Net-(U8-SW)") (class "Default")
      (node (ref "C17") (pin "2") (pinfunction "2_2") (pintype "passive"))
      (node (ref "L1") (pin "1") (pinfunction "1_1") (pintype "passive"))
      (node (ref "U8") (pin "8") (pinfunction "SW_8") (pintype "power_in"))
      (node (ref "ZD1") (pin "C") (pinfunction "C_C") (pintype "passive"))
    )
    (net (code "64") (name "SUPPLY_+3V3") (class "Default")
      (node (ref "C1") (pin "1") (pinfunction "1_1") (pintype "passive"))
      (node (ref "C10") (pin "2") (pinfunction "2_2") (pintype "passive"))
      (node (ref "C11") (pin "2") (pinfunction "2_2") (pintype "passive"))
      (node (ref "C13") (pin "1") (pinfunction "1_1") (pintype "passive"))
      (node (ref "C15") (pin "2") (pinfunction "2_2") (pintype "passive"))
      (node (ref "C16") (pin "2") (pinfunction "2_2") (pintype "passive"))
      (node (ref "C22") (pin "2") (pinfunction "2_2") (pintype "passive"))
      (node (ref "P10") (pin "1") (pinfunction "1_1") (pintype "passive"))
      (node (ref "P2") (pin "1") (pinfunction "1_1") (pintype "passive"))
      (node (ref "P3") (pin "1") (pinfunction "1_1") (pintype "passive"))
      (node (ref "P4") (pin "1") (pinfunction "1_1") (pintype "passive"))
      (node (ref "P7") (pin "3") (pinfunction "3_3") (pintype "passive"))
      (node (ref "P7") (pin "4") (pinfunction "4_4") (pintype "passive"))
      (node (ref "P9") (pin "2") (pinfunction "2_2") (pintype "passive"))
      (node (ref "R1") (pin "2") (pinfunction "2_2") (pintype "passive"))
      (node (ref "R12") (pin "1") (pinfunction "1_1") (pintype "passive"))
      (node (ref "R13") (pin "1") (pinfunction "1_1") (pintype "passive"))
      (node (ref "R15") (pin "2") (pinfunction "2_2") (pintype "passive"))
      (node (ref "R2") (pin "2") (pinfunction "2_2") (pintype "passive"))
      (node (ref "R3") (pin "1") (pinfunction "1_1") (pintype "passive"))
      (node (ref "R6") (pin "1") (pinfunction "1_1") (pintype "passive"))
      (node (ref "R7") (pin "2") (pinfunction "2_2") (pintype "passive"))
      (node (ref "R8") (pin "2") (pinfunction "2_2") (pintype "passive"))
      (node (ref "R9") (pin "1") (pinfunction "1_1") (pintype "passive"))
      (node (ref "U1") (pin "1") (pinfunction "VDD_1") (pintype "power_in"))
      (node (ref "U2") (pin "2") (pinfunction "VL_2") (pintype "input"))
      (node (ref "U2") (pin "23") (pinfunction "VCC_23") (pintype "power_in"))
      (node (ref "U3") (pin "17") (pinfunction "VCC_17") (pintype "power_in"))
      (node (ref "U3") (pin "27") (pinfunction "AVCC_27") (pintype "power_in"))
      (node (ref "U3") (pin "38") (pinfunction "VCC_38") (pintype "power_in"))
      (node (ref "U3") (pin "5") (pinfunction "VCC_5") (pintype "power_in"))
      (node (ref "U5") (pin "14") (pinfunction "3.3V_14") (pintype "power_in"))
      (node (ref "U6") (pin "19") (pinfunction "~{RESET}_19") (pintype "bidirectional"))
      (node (ref "U6") (pin "4") (pinfunction "VCCIO_4") (pintype "bidirectional"))
      (node (ref "U7") (pin "8") (pinfunction "VDD_8") (pintype "bidirectional"))
      (node (ref "U9") (pin "2") (pinfunction "OUT_2") (pintype "output"))
    )
    (net (code "65") (name "SUPPLY_+5V") (class "Default")
      (node (ref "C12") (pin "1") (pinfunction "1_1") (pintype "passive"))
      (node (ref "C18") (pin "+") (pinfunction "+_+") (pintype "passive"))
      (node (ref "C21") (pin "2") (pinfunction "2_2") (pintype "passive"))
      (node (ref "D1") (pin "C") (pinfunction "C_C") (pintype "passive"))
      (node (ref "L1") (pin "2") (pinfunction "2_2") (pintype "passive"))
      (node (ref "P6") (pin "2") (pinfunction "2_2") (pintype "passive"))
      (node (ref "P7") (pin "5") (pinfunction "5_5") (pintype "passive"))
      (node (ref "P7") (pin "6") (pinfunction "6_6") (pintype "passive"))
      (node (ref "Q1") (pin "2") (pinfunction "S_2") (pintype "passive"))
      (node (ref "R14") (pin "2") (pinfunction "2_2") (pintype "passive"))
      (node (ref "U4") (pin "5") (pinfunction "IN_5") (pintype "bidirectional"))
      (node (ref "U6") (pin "20") (pinfunction "VCC_20") (pintype "bidirectional"))
      (node (ref "U8") (pin "4") (pinfunction "FB_4") (pintype "bidirectional"))
      (node (ref "U9") (pin "3") (pinfunction "IN_3") (pintype "input"))
    )
    (net (code "66") (name "unconnected-(H1-MOUNT-PadB3,3)") (class "Default")
      (node (ref "H1") (pin "B3,3") (pinfunction "MOUNT_B3,3") (pintype "passive"))
    )
    (net (code "67") (name "unconnected-(H2-MOUNT-PadB3,3)") (class "Default")
      (node (ref "H2") (pin "B3,3") (pinfunction "MOUNT_B3,3") (pintype "passive"))
    )
    (net (code "68") (name "unconnected-(H3-MOUNT-PadB3,3)") (class "Default")
      (node (ref "H3") (pin "B3,3") (pinfunction "MOUNT_B3,3") (pintype "passive"))
    )
    (net (code "69") (name "unconnected-(H4-MOUNT-PadB3,3)") (class "Default")
      (node (ref "H4") (pin "B3,3") (pinfunction "MOUNT_B3,3") (pintype "passive"))
    )
    (net (code "70") (name "unconnected-(P5B-USBID-Pad4)") (class "Default")
      (node (ref "P5") (pin "4") (pinfunction "USBID_4") (pintype "bidirectional"))
    )
    (net (code "71") (name "unconnected-(P8-Pad13)") (class "Default")
      (node (ref "P8") (pin "13") (pinfunction "13_13") (pintype "passive"))
    )
    (net (code "72") (name "unconnected-(U2-GPIN1-Pad27)") (class "Default")
      (node (ref "U2") (pin "27") (pinfunction "GPIN1_27") (pintype "input"))
    )
    (net (code "73") (name "unconnected-(U2-GPIN2-Pad28)") (class "Default")
      (node (ref "U2") (pin "28") (pinfunction "GPIN2_28") (pintype "input"))
    )
    (net (code "74") (name "unconnected-(U2-GPIN3-Pad29)") (class "Default")
      (node (ref "U2") (pin "29") (pinfunction "GPIN3_29") (pintype "input"))
    )
    (net (code "75") (name "unconnected-(U2-GPIN4-Pad30)") (class "Default")
      (node (ref "U2") (pin "30") (pinfunction "GPIN4_30") (pintype "input"))
    )
    (net (code "76") (name "unconnected-(U2-GPIN5-Pad31)") (class "Default")
      (node (ref "U2") (pin "31") (pinfunction "GPIN5_31") (pintype "input"))
    )
    (net (code "77") (name "unconnected-(U2-GPIN6-Pad32)") (class "Default")
      (node (ref "U2") (pin "32") (pinfunction "GPIN6_32") (pintype "input"))
    )
    (net (code "78") (name "unconnected-(U2-GPIN7-Pad1)") (class "Default")
      (node (ref "U2") (pin "1") (pinfunction "GPIN7_1") (pintype "input"))
    )
    (net (code "79") (name "unconnected-(U2-GPOUT1-Pad5)") (class "Default")
      (node (ref "U2") (pin "5") (pinfunction "GPOUT1_5") (pintype "output"))
    )
    (net (code "80") (name "unconnected-(U2-GPOUT2-Pad6)") (class "Default")
      (node (ref "U2") (pin "6") (pinfunction "GPOUT2_6") (pintype "output"))
    )
    (net (code "81") (name "unconnected-(U2-GPOUT3-Pad7)") (class "Default")
      (node (ref "U2") (pin "7") (pinfunction "GPOUT3_7") (pintype "output"))
    )
    (net (code "82") (name "unconnected-(U2-GPOUT4-Pad8)") (class "Default")
      (node (ref "U2") (pin "8") (pinfunction "GPOUT4_8") (pintype "output"))
    )
    (net (code "83") (name "unconnected-(U2-GPOUT5-Pad9)") (class "Default")
      (node (ref "U2") (pin "9") (pinfunction "GPOUT5_9") (pintype "output"))
    )
    (net (code "84") (name "unconnected-(U2-GPOUT6-Pad10)") (class "Default")
      (node (ref "U2") (pin "10") (pinfunction "GPOUT6_10") (pintype "output"))
    )
    (net (code "85") (name "unconnected-(U2-GPOUT7-Pad11)") (class "Default")
      (node (ref "U2") (pin "11") (pinfunction "GPOUT7_11") (pintype "output"))
    )
    (net (code "86") (name "unconnected-(U2-GPX-Pad17)") (class "Default")
      (node (ref "U2") (pin "17") (pinfunction "GPX_17") (pintype "output"))
    )
    (net (code "87") (name "unconnected-(U2-VBCOMP-Pad22)") (class "Default")
      (node (ref "U2") (pin "22") (pinfunction "VBCOMP_22") (pintype "input"))
    )
    (net (code "88") (name "unconnected-(U3-(PCINT8{slash}XCK0{slash}T0)PB0-Pad40)") (class "Default")
      (node (ref "U3") (pin "40") (pinfunction "(PCINT8/XCK0/T0)PB0_40") (pintype "bidirectional"))
    )
    (net (code "89") (name "unconnected-(U3-(PCINT9{slash}CLKO{slash}T1)PB1-Pad41)") (class "Default")
      (node (ref "U3") (pin "41") (pinfunction "(PCINT9/CLKO/T1)PB1_41") (pintype "bidirectional"))
    )
    (net (code "90") (name "unconnected-(U3-(PCINT21{slash}TDI)PC5-Pad24)") (class "Default")
      (node (ref "U3") (pin "24") (pinfunction "(PCINT21/TDI)PC5_24") (pintype "output"))
    )
    (net (code "91") (name "unconnected-(U3-(PCINT22{slash}TOSC1)PC6-Pad25)") (class "Default")
      (node (ref "U3") (pin "25") (pinfunction "(PCINT22/TOSC1)PC6_25") (pintype "output"))
    )
    (net (code "92") (name "unconnected-(U3-(PCINT23{slash}TOSC2)PC7-Pad26)") (class "Default")
      (node (ref "U3") (pin "26") (pinfunction "(PCINT23/TOSC2)PC7_26") (pintype "output"))
    )
    (net (code "93") (name "unconnected-(U5-4Y-Pad11)") (class "Default")
      (node (ref "U5") (pin "11") (pinfunction "4Y_11") (pintype "output"))
    )
    (net (code "94") (name "unconnected-(U6-3V3OUT-Pad17)") (class "Default")
      (node (ref "U6") (pin "17") (pinfunction "3V3OUT_17") (pintype "bidirectional"))
    )
    (net (code "95") (name "unconnected-(U6-OSCI-Pad27)") (class "Default")
      (node (ref "U6") (pin "27") (pinfunction "OSCI_27") (pintype "bidirectional"))
    )
    (net (code "96") (name "unconnected-(U6-OSCO-Pad28)") (class "Default")
      (node (ref "U6") (pin "28") (pinfunction "OSCO_28") (pintype "bidirectional"))
    )
    (net (code "97") (name "unconnected-(U6-TXDEN-Pad13)") (class "Default")
      (node (ref "U6") (pin "13") (pinfunction "TXDEN_13") (pintype "bidirectional"))
    )
    (net (code "98") (name "unconnected-(U6-~{CTS}-Pad11)") (class "Default")
      (node (ref "U6") (pin "11") (pinfunction "~{CTS}_11") (pintype "bidirectional"))
    )
    (net (code "99") (name "unconnected-(U6-~{DCD}-Pad10)") (class "Default")
      (node (ref "U6") (pin "10") (pinfunction "~{DCD}_10") (pintype "bidirectional"))
    )
    (net (code "100") (name "unconnected-(U6-~{DSR}-Pad9)") (class "Default")
      (node (ref "U6") (pin "9") (pinfunction "~{DSR}_9") (pintype "bidirectional"))
    )
    (net (code "101") (name "unconnected-(U6-~{PWREN}-Pad14)") (class "Default")
      (node (ref "U6") (pin "14") (pinfunction "~{PWREN}_14") (pintype "bidirectional"))
    )
    (net (code "102") (name "unconnected-(U6-~{RI}-Pad6)") (class "Default")
      (node (ref "U6") (pin "6") (pinfunction "~{RI}_6") (pintype "bidirectional"))
    )
    (net (code "103") (name "unconnected-(U6-~{RTS}-Pad3)") (class "Default")
      (node (ref "U6") (pin "3") (pinfunction "~{RTS}_3") (pintype "bidirectional"))
    )
    (net (code "104") (name "unconnected-(U6-~{SLEEP}-Pad12)") (class "Default")
      (node (ref "U6") (pin "12") (pinfunction "~{SLEEP}_12") (pintype "bidirectional"))
    )
  )
)
